# SPARC_Project_Gamma_Schematic.net
KiCad netlist of a schematic drawn in EAGLE
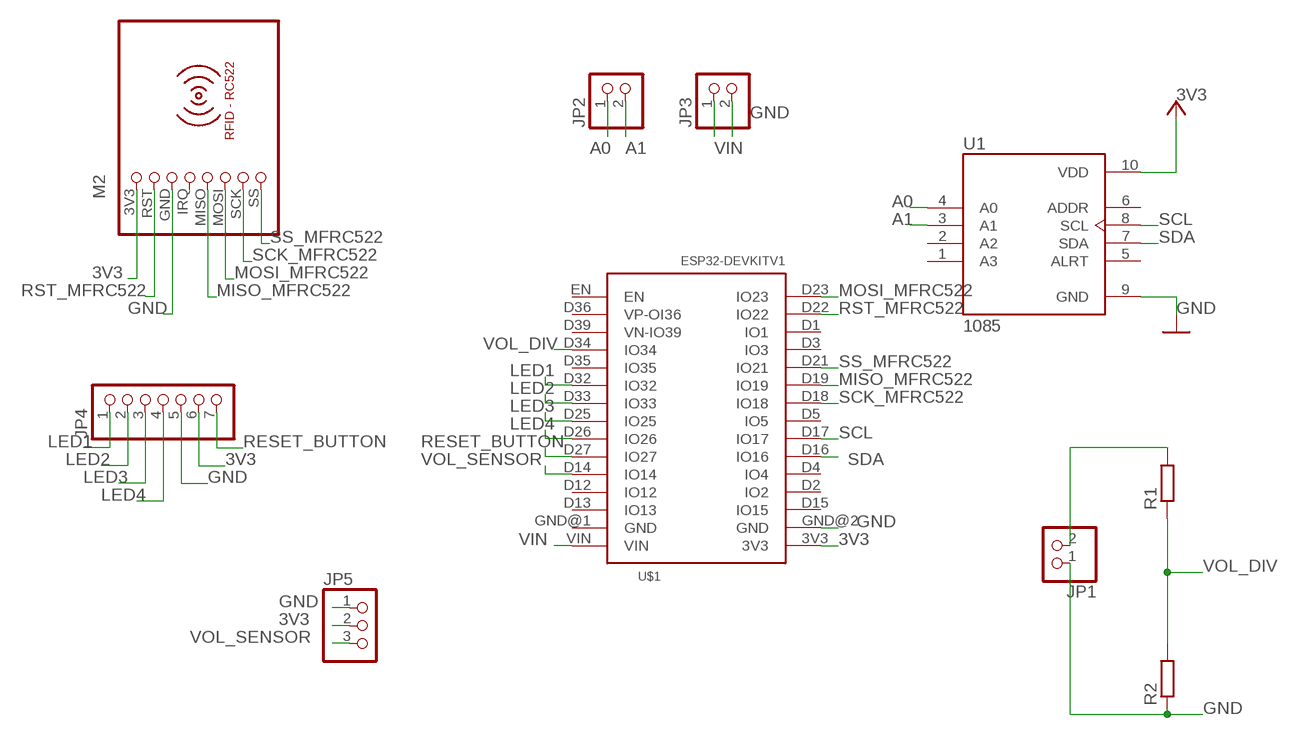
[diagram p0: schematic, sheet 1]

(export (version "E")
  (design (tool "Eeschema 10.0.6"))
  (components
    (comp (ref "JP1")
      (value "PINHD-1X2")
      (footprint "eagle-import:1X02")
      (libsource (lib "eagle-import") (part "PINHD-1X2"))
    )
    (comp (ref "JP2")
      (value "PINHD-1X2")
      (footprint "eagle-import:1X02")
      (libsource (lib "eagle-import") (part "PINHD-1X2"))
    )
    (comp (ref "JP3")
      (value "PINHD-1X2")
      (footprint "eagle-import:1X02")
      (libsource (lib "eagle-import") (part "PINHD-1X2"))
    )
    (comp (ref "JP4")
      (value "PINHD-1X7")
      (footprint "eagle-import:1X07")
      (libsource (lib "eagle-import") (part "PINHD-1X7"))
    )
    (comp (ref "JP5")
      (value "PINHD-1X3")
      (footprint "eagle-import:1X03")
      (libsource (lib "eagle-import") (part "PINHD-1X3"))
    )
    (comp (ref "M2")
      (value "RFID-RC522")
      (footprint "eagle-import:RFID-RC522")
      (libsource (lib "eagle-import") (part "RFID-RC522"))
    )
    (comp (ref "R1")
      (value "R-EU_0204/2V")
      (footprint "eagle-import:0204V")
      (libsource (lib "eagle-import") (part "R-EU_0204/2V"))
    )
    (comp (ref "R2")
      (value "R-EU_0204/2V")
      (footprint "eagle-import:0204V")
      (libsource (lib "eagle-import") (part "R-EU_0204/2V"))
    )
    (comp (ref "U$1")
      (value "ESP32DEVKITV1")
      (footprint "eagle-import:ESP32-DEVKITV1")
      (libsource (lib "eagle-import") (part "ESP32DEVKITV1"))
    )
    (comp (ref "U1")
      (value "1085")
      (footprint "eagle-import:MODULE_1085")
      (fields (field (name "MF") "Adafruit Industries"))
      (libsource (lib "eagle-import") (part "1085"))
    )
  )
  (nets
    (net (code "1") (name "+3V3") (class "Default")
      (node (ref "JP4") (pin "6") (pinfunction "6_6") (pintype "passive"))
      (node (ref "JP5") (pin "2") (pinfunction "2_2") (pintype "passive"))
      (node (ref "M2") (pin "3V3") (pinfunction "1_3V3") (pintype "passive"))
      (node (ref "U$1") (pin "3V3") (pinfunction "3V3_3V3") (pintype "bidirectional"))
      (node (ref "U1") (pin "10") (pinfunction "VDD_10") (pintype "power_in"))
    )
    (net (code "2") (name "/A0") (class "Default")
      (node (ref "JP2") (pin "1") (pinfunction "1_1") (pintype "passive"))
      (node (ref "U1") (pin "4") (pinfunction "A0_4") (pintype "input"))
    )
    (net (code "3") (name "/A1") (class "Default")
      (node (ref "JP2") (pin "2") (pinfunction "2_2") (pintype "passive"))
      (node (ref "U1") (pin "3") (pinfunction "A1_3") (pintype "input"))
    )
    (net (code "4") (name "/LED1") (class "Default")
      (node (ref "JP4") (pin "1") (pinfunction "1_1") (pintype "passive"))
      (node (ref "U$1") (pin "D32") (pinfunction "IO32_D32") (pintype "bidirectional"))
    )
    (net (code "5") (name "/LED2") (class "Default")
      (node (ref "JP4") (pin "2") (pinfunction "2_2") (pintype "passive"))
      (node (ref "U$1") (pin "D33") (pinfunction "IO33_D33") (pintype "bidirectional"))
    )
    (net (code "6") (name "/LED3") (class "Default")
      (node (ref "JP4") (pin "3") (pinfunction "3_3") (pintype "passive"))
      (node (ref "U$1") (pin "D25") (pinfunction "IO25_D25") (pintype "bidirectional"))
    )
    (net (code "7") (name "/LED4") (class "Default")
      (node (ref "JP4") (pin "4") (pinfunction "4_4") (pintype "passive"))
      (node (ref "U$1") (pin "D26") (pinfunction "IO26_D26") (pintype "bidirectional"))
    )
    (net (code "8") (name "/MISO_MFRC522") (class "Default")
      (node (ref "M2") (pin "MISO") (pinfunction "5_MISO") (pintype "passive"))
      (node (ref "U$1") (pin "D19") (pinfunction "IO19_D19") (pintype "bidirectional"))
    )
    (net (code "9") (name "/MOSI_MFRC522") (class "Default")
      (node (ref "M2") (pin "MOSI") (pinfunction "6_MOSI") (pintype "passive"))
      (node (ref "U$1") (pin "D23") (pinfunction "IO23_D23") (pintype "bidirectional"))
    )
    (net (code "10") (name "/RESET_BUTTON") (class "Default")
      (node (ref "JP4") (pin "7") (pinfunction "7_7") (pintype "passive"))
      (node (ref "U$1") (pin "D27") (pinfunction "IO27_D27") (pintype "bidirectional"))
    )
    (net (code "11") (name "/RST_MFRC522") (class "Default")
      (node (ref "M2") (pin "RST") (pinfunction "2_RST") (pintype "passive"))
      (node (ref "U$1") (pin "D22") (pinfunction "IO22_D22") (pintype "bidirectional"))
    )
    (net (code "12") (name "/SCK_MFRC522") (class "Default")
      (node (ref "M2") (pin "SCK") (pinfunction "7_SCK") (pintype "passive"))
      (node (ref "U$1") (pin "D18") (pinfunction "IO18_D18") (pintype "bidirectional"))
    )
    (net (code "13") (name "/SCL") (class "Default")
      (node (ref "U$1") (pin "D17") (pinfunction "IO17_D17") (pintype "bidirectional"))
      (node (ref "U1") (pin "8") (pinfunction "SCL_8") (pintype "input"))
    )
    (net (code "14") (name "/SDA") (class "Default")
      (node (ref "U$1") (pin "D16") (pinfunction "IO16_D16") (pintype "bidirectional"))
      (node (ref "U1") (pin "7") (pinfunction "SDA_7") (pintype "bidirectional"))
    )
    (net (code "15") (name "/SS_MFRC522") (class "Default")
      (node (ref "M2") (pin "SS") (pinfunction "8_SS") (pintype "passive"))
      (node (ref "U$1") (pin "D21") (pinfunction "IO21_D21") (pintype "bidirectional"))
    )
    (net (code "16") (name "/VIN") (class "Default")
      (node (ref "JP3") (pin "1") (pinfunction "1_1") (pintype "passive"))
      (node (ref "U$1") (pin "VIN") (pinfunction "VIN_VIN") (pintype "bidirectional"))
    )
    (net (code "17") (name "/VOL_DIV") (class "Default")
      (node (ref "R1") (pin "1") (pinfunction "1_1") (pintype "passive"))
      (node (ref "R2") (pin "2") (pinfunction "2_2") (pintype "passive"))
      (node (ref "U$1") (pin "D34") (pinfunction "IO34_D34") (pintype "bidirectional"))
    )
    (net (code "18") (name "/VOL_SENSOR") (class "Default")
      (node (ref "JP5") (pin "3") (pinfunction "3_3") (pintype "passive"))
      (node (ref "U$1") (pin "D14") (pinfunction "IO14_D14") (pintype "bidirectional"))
    )
    (net (code "19") (name "GND") (class "Default")
      (node (ref "JP1") (pin "1") (pinfunction "1_1") (pintype "passive"))
      (node (ref "JP3") (pin "2") (pinfunction "2_2") (pintype "passive"))
      (node (ref "JP4") (pin "5") (pinfunction "5_5") (pintype "passive"))
      (node (ref "JP5") (pin "1") (pinfunction "1_1") (pintype "passive"))
      (node (ref "M2") (pin "GND") (pinfunction "3_GND") (pintype "passive"))
      (node (ref "R2") (pin "1") (pinfunction "1_1") (pintype "passive"))
      (node (ref "U$1") (pin "GND@2") (pinfunction "GND_GND@2") (pintype "bidirectional"))
      (node (ref "U1") (pin "9") (pinfunction "GND_9") (pintype "power_in"))
    )
    (net (code "20") (name "Net-(JP1-Pad2)") (class "Default")
      (node (ref "JP1") (pin "2") (pinfunction "2_2") (pintype "passive"))
      (node (ref "R1") (pin "2") (pinfunction "2_2") (pintype "passive"))
    )
    (net (code "21") (name "unconnected-(M2-4-PadIRQ)") (class "Default")
      (node (ref "M2") (pin "IRQ") (pinfunction "4_IRQ") (pintype "passive"))
    )
    (net (code "22") (name "unconnected-(U$1-GND-PadGND@1)") (class "Default")
      (node (ref "U$1") (pin "GND@1") (pinfunction "GND_GND@1") (pintype "bidirectional"))
    )
    (net (code "23") (name "unconnected-(U$1-IO1-PadD1)") (class "Default")
      (node (ref "U$1") (pin "D1") (pinfunction "IO1_D1") (pintype "bidirectional"))
    )
    (net (code "24") (name "unconnected-(U$1-IO2-PadD2)") (class "Default")
      (node (ref "U$1") (pin "D2") (pinfunction "IO2_D2") (pintype "bidirectional"))
    )
    (net (code "25") (name "unconnected-(U$1-IO3-PadD3)") (class "Default")
      (node (ref "U$1") (pin "D3") (pinfunction "IO3_D3") (pintype "bidirectional"))
    )
    (net (code "26") (name "unconnected-(U$1-IO4-PadD4)") (class "Default")
      (node (ref "U$1") (pin "D4") (pinfunction "IO4_D4") (pintype "bidirectional"))
    )
    (net (code "27") (name "unconnected-(U$1-IO5-PadD5)") (class "Default")
      (node (ref "U$1") (pin "D5") (pinfunction "IO5_D5") (pintype "bidirectional"))
    )
    (net (code "28") (name "unconnected-(U$1-IO12-PadD12)") (class "Default")
      (node (ref "U$1") (pin "D12") (pinfunction "IO12_D12") (pintype "bidirectional"))
    )
    (net (code "29") (name "unconnected-(U$1-IO13-PadD13)") (class "Default")
      (node (ref "U$1") (pin "D13") (pinfunction "IO13_D13") (pintype "bidirectional"))
    )
    (net (code "30") (name "unconnected-(U$1-IO15-PadD15)") (class "Default")
      (node (ref "U$1") (pin "D15") (pinfunction "IO15_D15") (pintype "bidirectional"))
    )
    (net (code "31") (name "unconnected-(U$1-IO35-PadD35)") (class "Default")
      (node (ref "U$1") (pin "D35") (pinfunction "IO35_D35") (pintype "bidirectional"))
    )
    (net (code "32") (name "unconnected-(U$1-PadEN)") (class "Default")
      (node (ref "U$1") (pin "EN") (pinfunction "EN_EN") (pintype "bidirectional"))
    )
    (net (code "33") (name "unconnected-(U$1-VN-IO39-PadD39)") (class "Default")
      (node (ref "U$1") (pin "D39") (pinfunction "VN-IO39_D39") (pintype "bidirectional"))
    )
    (net (code "34") (name "unconnected-(U$1-VP-OI36-PadD36)") (class "Default")
      (node (ref "U$1") (pin "D36") (pinfunction "VP-OI36_D36") (pintype "bidirectional"))
    )
    (net (code "35") (name "unconnected-(U1-A2-Pad2)") (class "Default")
      (node (ref "U1") (pin "2") (pinfunction "A2_2") (pintype "input"))
    )
    (net (code "36") (name "unconnected-(U1-A3-Pad1)") (class "Default")
      (node (ref "U1") (pin "1") (pinfunction "A3_1") (pintype "input"))
    )
    (net (code "37") (name "unconnected-(U1-ADDR-Pad6)") (class "Default")
      (node (ref "U1") (pin "6") (pinfunction "ADDR_6") (pintype "input"))
    )
    (net (code "38") (name "unconnected-(U1-ALRT-Pad5)") (class "Default")
      (node (ref "U1") (pin "5") (pinfunction "ALRT_5") (pintype "output"))
    )
  )
)
